# sterownik_led.net
KiCad netlist of a schematic drawn in EAGLE
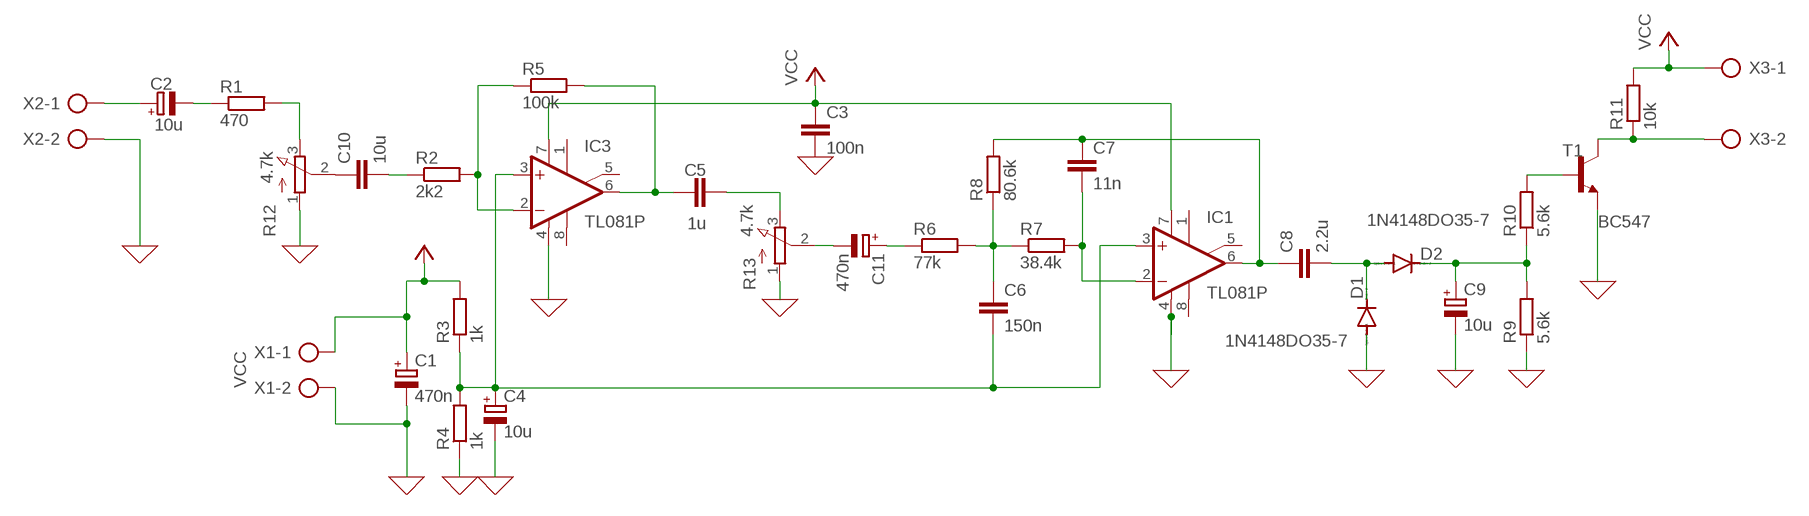
[diagram p0: schematic, sheet 1]

(export (version "E")
  (design (tool "Eeschema 10.0.6"))
  (components
    (comp (ref "C1")
      (value "470n")
      (footprint "eagle-import:TT2D7")
      (libsource (lib "eagle-import") (part "CPOL-EUTT2D7"))
    )
    (comp (ref "C2")
      (value "10u")
      (footprint "eagle-import:TT2D7")
      (libsource (lib "eagle-import") (part "CPOL-EUTT2D7"))
    )
    (comp (ref "C3")
      (value "100n")
      (footprint "eagle-import:C025-025X050")
      (libsource (lib "eagle-import") (part "C-EU025-025X050"))
    )
    (comp (ref "C4")
      (value "10u")
      (footprint "eagle-import:TT2D7")
      (libsource (lib "eagle-import") (part "CPOL-EUTT2D7"))
    )
    (comp (ref "C5")
      (value "1u")
      (footprint "eagle-import:C025-025X050")
      (libsource (lib "eagle-import") (part "C-EU025-025X050"))
    )
    (comp (ref "C6")
      (value "150n")
      (footprint "eagle-import:C025-025X050")
      (libsource (lib "eagle-import") (part "C-EU025-025X050"))
    )
    (comp (ref "C7")
      (value "11n")
      (footprint "eagle-import:C025-025X050")
      (libsource (lib "eagle-import") (part "C-EU025-025X050"))
    )
    (comp (ref "C8")
      (value "2.2u")
      (footprint "eagle-import:C025-025X050")
      (libsource (lib "eagle-import") (part "C-EU025-025X050"))
    )
    (comp (ref "C9")
      (value "10u")
      (footprint "eagle-import:TT2D7")
      (libsource (lib "eagle-import") (part "CPOL-EUTT2D7"))
    )
    (comp (ref "C10")
      (value "10u")
      (footprint "eagle-import:C050-025X075")
      (libsource (lib "eagle-import") (part "C-EU050-025X075"))
    )
    (comp (ref "C11")
      (value "470n")
      (footprint "eagle-import:TT2D7")
      (libsource (lib "eagle-import") (part "CPOL-EUTT2D7"))
    )
    (comp (ref "D1")
      (value "1N4148DO35-7")
      (footprint "eagle-import:DO35-7")
      (libsource (lib "eagle-import") (part "1N4148DO35-7"))
    )
    (comp (ref "D2")
      (value "1N4148DO35-7")
      (footprint "eagle-import:DO35-7")
      (libsource (lib "eagle-import") (part "1N4148DO35-7"))
    )
    (comp (ref "IC1")
      (value "TL081P")
      (footprint "eagle-import:DIL08")
      (libsource (lib "eagle-import") (part "TL081P"))
    )
    (comp (ref "IC3")
      (value "TL081P")
      (footprint "eagle-import:DIL08")
      (libsource (lib "eagle-import") (part "TL081P"))
    )
    (comp (ref "R1")
      (value "470")
      (footprint "eagle-import:0207_10")
      (libsource (lib "eagle-import") (part "R-EU_0207/10"))
    )
    (comp (ref "R2")
      (value "2k2")
      (footprint "eagle-import:0207_10")
      (libsource (lib "eagle-import") (part "R-EU_0207/10"))
    )
    (comp (ref "R3")
      (value "1k")
      (footprint "eagle-import:0207_10")
      (libsource (lib "eagle-import") (part "R-EU_0207/10"))
    )
    (comp (ref "R4")
      (value "1k")
      (footprint "eagle-import:0207_10")
      (libsource (lib "eagle-import") (part "R-EU_0207/10"))
    )
    (comp (ref "R5")
      (value "100k")
      (footprint "eagle-import:0207_10")
      (libsource (lib "eagle-import") (part "R-EU_0207/10"))
    )
    (comp (ref "R6")
      (value "77k")
      (footprint "eagle-import:0207_10")
      (libsource (lib "eagle-import") (part "R-EU_0207/10"))
    )
    (comp (ref "R7")
      (value "38.4k")
      (footprint "eagle-import:0207_10")
      (libsource (lib "eagle-import") (part "R-EU_0207/10"))
    )
    (comp (ref "R8")
      (value "80.6k")
      (footprint "eagle-import:0207_10")
      (libsource (lib "eagle-import") (part "R-EU_0207/10"))
    )
    (comp (ref "R9")
      (value "5.6k")
      (footprint "eagle-import:0207_10")
      (libsource (lib "eagle-import") (part "R-EU_0207/10"))
    )
    (comp (ref "R10")
      (value "5.6k")
      (footprint "eagle-import:0207_10")
      (libsource (lib "eagle-import") (part "R-EU_0207/10"))
    )
    (comp (ref "R11")
      (value "10k")
      (footprint "eagle-import:0207_10")
      (libsource (lib "eagle-import") (part "R-EU_0207/10"))
    )
    (comp (ref "R12")
      (value "4.7k")
      (footprint "eagle-import:3RP_1610N")
      (libsource (lib "eagle-import") (part "3RP/1610N"))
    )
    (comp (ref "R13")
      (value "4.7k")
      (footprint "eagle-import:3RP_1610N")
      (libsource (lib "eagle-import") (part "3RP/1610N"))
    )
    (comp (ref "T1")
      (value "BC547")
      (footprint "eagle-import:TO92")
      (libsource (lib "eagle-import") (part "BC547"))
    )
    (comp (ref "X1")
      (value "AK500/2")
      (footprint "eagle-import:AK500_2")
      (libsource (lib "eagle-import") (part "AK500/2"))
    )
    (comp (ref "X2")
      (value "AK500/2")
      (footprint "eagle-import:AK500_2")
      (libsource (lib "eagle-import") (part "AK500/2"))
    )
    (comp (ref "X3")
      (value "AK500/2")
      (footprint "eagle-import:AK500_2")
      (libsource (lib "eagle-import") (part "AK500/2"))
    )
  )
  (nets
    (net (code "1") (name "GND") (class "Default")
      (node (ref "C1") (pin "-") (pinfunction "-_-") (pintype "passive"))
      (node (ref "C3") (pin "2") (pinfunction "2_2") (pintype "passive"))
      (node (ref "C4") (pin "-") (pinfunction "-_-") (pintype "passive"))
      (node (ref "C9") (pin "-") (pinfunction "-_-") (pintype "passive"))
      (node (ref "D1") (pin "A") (pinfunction "A_A") (pintype "passive"))
      (node (ref "IC1") (pin "4") (pinfunction "V-_4") (pintype "power_in"))
      (node (ref "IC3") (pin "4") (pinfunction "V-_4") (pintype "power_in"))
      (node (ref "R12") (pin "1") (pinfunction "A_1") (pintype "passive"))
      (node (ref "R13") (pin "1") (pinfunction "A_1") (pintype "passive"))
      (node (ref "R4") (pin "1") (pinfunction "1_1") (pintype "passive"))
      (node (ref "R9") (pin "1") (pinfunction "1_1") (pintype "passive"))
      (node (ref "T1") (pin "1") (pinfunction "E_1") (pintype "passive"))
      (node (ref "X1") (pin "2") (pinfunction "KL_2") (pintype "passive"))
      (node (ref "X2") (pin "2") (pinfunction "KL_2") (pintype "passive"))
    )
    (net (code "2") (name "Net-(C2-Pad-)") (class "Default")
      (node (ref "C2") (pin "-") (pinfunction "-_-") (pintype "passive"))
      (node (ref "R1") (pin "1") (pinfunction "1_1") (pintype "passive"))
    )
    (net (code "3") (name "Net-(C6-Pad1)") (class "Default")
      (node (ref "C6") (pin "1") (pinfunction "1_1") (pintype "passive"))
      (node (ref "R6") (pin "2") (pinfunction "2_2") (pintype "passive"))
      (node (ref "R7") (pin "1") (pinfunction "1_1") (pintype "passive"))
      (node (ref "R8") (pin "1") (pinfunction "1_1") (pintype "passive"))
    )
    (net (code "4") (name "Net-(C8-Pad2)") (class "Default")
      (node (ref "C8") (pin "2") (pinfunction "2_2") (pintype "passive"))
      (node (ref "D1") (pin "C") (pinfunction "C_C") (pintype "passive"))
      (node (ref "D2") (pin "A") (pinfunction "A_A") (pintype "passive"))
    )
    (net (code "5") (name "Net-(C9-Pad+)") (class "Default")
      (node (ref "C9") (pin "+") (pinfunction "+_+") (pintype "passive"))
      (node (ref "D2") (pin "C") (pinfunction "C_C") (pintype "passive"))
      (node (ref "R10") (pin "1") (pinfunction "1_1") (pintype "passive"))
      (node (ref "R9") (pin "2") (pinfunction "2_2") (pintype "passive"))
    )
    (net (code "6") (name "Net-(C10-Pad2)") (class "Default")
      (node (ref "C10") (pin "2") (pinfunction "2_2") (pintype "passive"))
      (node (ref "R2") (pin "1") (pinfunction "1_1") (pintype "passive"))
    )
    (net (code "7") (name "Net-(C11-Pad+)") (class "Default")
      (node (ref "C11") (pin "+") (pinfunction "+_+") (pintype "passive"))
      (node (ref "R6") (pin "1") (pinfunction "1_1") (pintype "passive"))
    )
    (net (code "8") (name "Net-(IC1-+IN)") (class "Default")
      (node (ref "C4") (pin "+") (pinfunction "+_+") (pintype "passive"))
      (node (ref "C6") (pin "2") (pinfunction "2_2") (pintype "passive"))
      (node (ref "IC1") (pin "3") (pinfunction "+IN_3") (pintype "input"))
      (node (ref "IC3") (pin "3") (pinfunction "+IN_3") (pintype "input"))
      (node (ref "R3") (pin "1") (pinfunction "1_1") (pintype "passive"))
      (node (ref "R4") (pin "2") (pinfunction "2_2") (pintype "passive"))
    )
    (net (code "9") (name "Net-(IC1--IN)") (class "Default")
      (node (ref "C7") (pin "2") (pinfunction "2_2") (pintype "passive"))
      (node (ref "IC1") (pin "2") (pinfunction "-IN_2") (pintype "input"))
      (node (ref "R7") (pin "2") (pinfunction "2_2") (pintype "passive"))
    )
    (net (code "10") (name "Net-(IC1-OUT)") (class "Default")
      (node (ref "C7") (pin "1") (pinfunction "1_1") (pintype "passive"))
      (node (ref "C8") (pin "1") (pinfunction "1_1") (pintype "passive"))
      (node (ref "IC1") (pin "6") (pinfunction "OUT_6") (pintype "output"))
      (node (ref "R8") (pin "2") (pinfunction "2_2") (pintype "passive"))
    )
    (net (code "11") (name "Net-(IC3--IN)") (class "Default")
      (node (ref "IC3") (pin "2") (pinfunction "-IN_2") (pintype "input"))
      (node (ref "R2") (pin "2") (pinfunction "2_2") (pintype "passive"))
      (node (ref "R5") (pin "1") (pinfunction "1_1") (pintype "passive"))
    )
    (net (code "12") (name "Net-(IC3-OUT)") (class "Default")
      (node (ref "C5") (pin "1") (pinfunction "1_1") (pintype "passive"))
      (node (ref "IC3") (pin "6") (pinfunction "OUT_6") (pintype "output"))
      (node (ref "R5") (pin "2") (pinfunction "2_2") (pintype "passive"))
    )
    (net (code "13") (name "Net-(R12-E)") (class "Default")
      (node (ref "R1") (pin "2") (pinfunction "2_2") (pintype "passive"))
      (node (ref "R12") (pin "3") (pinfunction "E_3") (pintype "passive"))
    )
    (net (code "14") (name "Net-(R12-S)") (class "Default")
      (node (ref "C10") (pin "1") (pinfunction "1_1") (pintype "passive"))
      (node (ref "R12") (pin "2") (pinfunction "S_2") (pintype "passive"))
    )
    (net (code "15") (name "Net-(R13-E)") (class "Default")
      (node (ref "C5") (pin "2") (pinfunction "2_2") (pintype "passive"))
      (node (ref "R13") (pin "3") (pinfunction "E_3") (pintype "passive"))
    )
    (net (code "16") (name "Net-(R13-S)") (class "Default")
      (node (ref "C11") (pin "-") (pinfunction "-_-") (pintype "passive"))
      (node (ref "R13") (pin "2") (pinfunction "S_2") (pintype "passive"))
    )
    (net (code "17") (name "Net-(T1-B)") (class "Default")
      (node (ref "R10") (pin "2") (pinfunction "2_2") (pintype "passive"))
      (node (ref "T1") (pin "2") (pinfunction "B_2") (pintype "passive"))
    )
    (net (code "18") (name "Net-(T1-C)") (class "Default")
      (node (ref "R11") (pin "1") (pinfunction "1_1") (pintype "passive"))
      (node (ref "T1") (pin "3") (pinfunction "C_3") (pintype "passive"))
      (node (ref "X3") (pin "2") (pinfunction "KL_2") (pintype "passive"))
    )
    (net (code "19") (name "Net-(X2A-KL)") (class "Default")
      (node (ref "C2") (pin "+") (pinfunction "+_+") (pintype "passive"))
      (node (ref "X2") (pin "1") (pinfunction "KL_1") (pintype "passive"))
    )
    (net (code "20") (name "VCC") (class "Default")
      (node (ref "C1") (pin "+") (pinfunction "+_+") (pintype "passive"))
      (node (ref "C3") (pin "1") (pinfunction "1_1") (pintype "passive"))
      (node (ref "IC1") (pin "7") (pinfunction "V+_7") (pintype "power_in"))
      (node (ref "IC3") (pin "7") (pinfunction "V+_7") (pintype "power_in"))
      (node (ref "R11") (pin "2") (pinfunction "2_2") (pintype "passive"))
      (node (ref "R3") (pin "2") (pinfunction "2_2") (pintype "passive"))
      (node (ref "X1") (pin "1") (pinfunction "KL_1") (pintype "passive"))
      (node (ref "X3") (pin "1") (pinfunction "KL_1") (pintype "passive"))
    )
    (net (code "21") (name "unconnected-(IC1-ON1-Pad1)") (class "Default")
      (node (ref "IC1") (pin "1") (pinfunction "ON1_1") (pintype "passive"))
    )
    (net (code "22") (name "unconnected-(IC1-ON2-Pad5)") (class "Default")
      (node (ref "IC1") (pin "5") (pinfunction "ON2_5") (pintype "passive"))
    )
    (net (code "23") (name "unconnected-(IC1-OPT-Pad8)") (class "Default")
      (node (ref "IC1") (pin "8") (pinfunction "OPT_8") (pintype "passive"))
    )
    (net (code "24") (name "unconnected-(IC3-ON1-Pad1)") (class "Default")
      (node (ref "IC3") (pin "1") (pinfunction "ON1_1") (pintype "passive"))
    )
    (net (code "25") (name "unconnected-(IC3-ON2-Pad5)") (class "Default")
      (node (ref "IC3") (pin "5") (pinfunction "ON2_5") (pintype "passive"))
    )
    (net (code "26") (name "unconnected-(IC3-OPT-Pad8)") (class "Default")
      (node (ref "IC3") (pin "8") (pinfunction "OPT_8") (pintype "passive"))
    )
  )
)
